# nRF24L01_RFX2401_SMD_0603.net
KiCad netlist of a schematic drawn in EAGLE
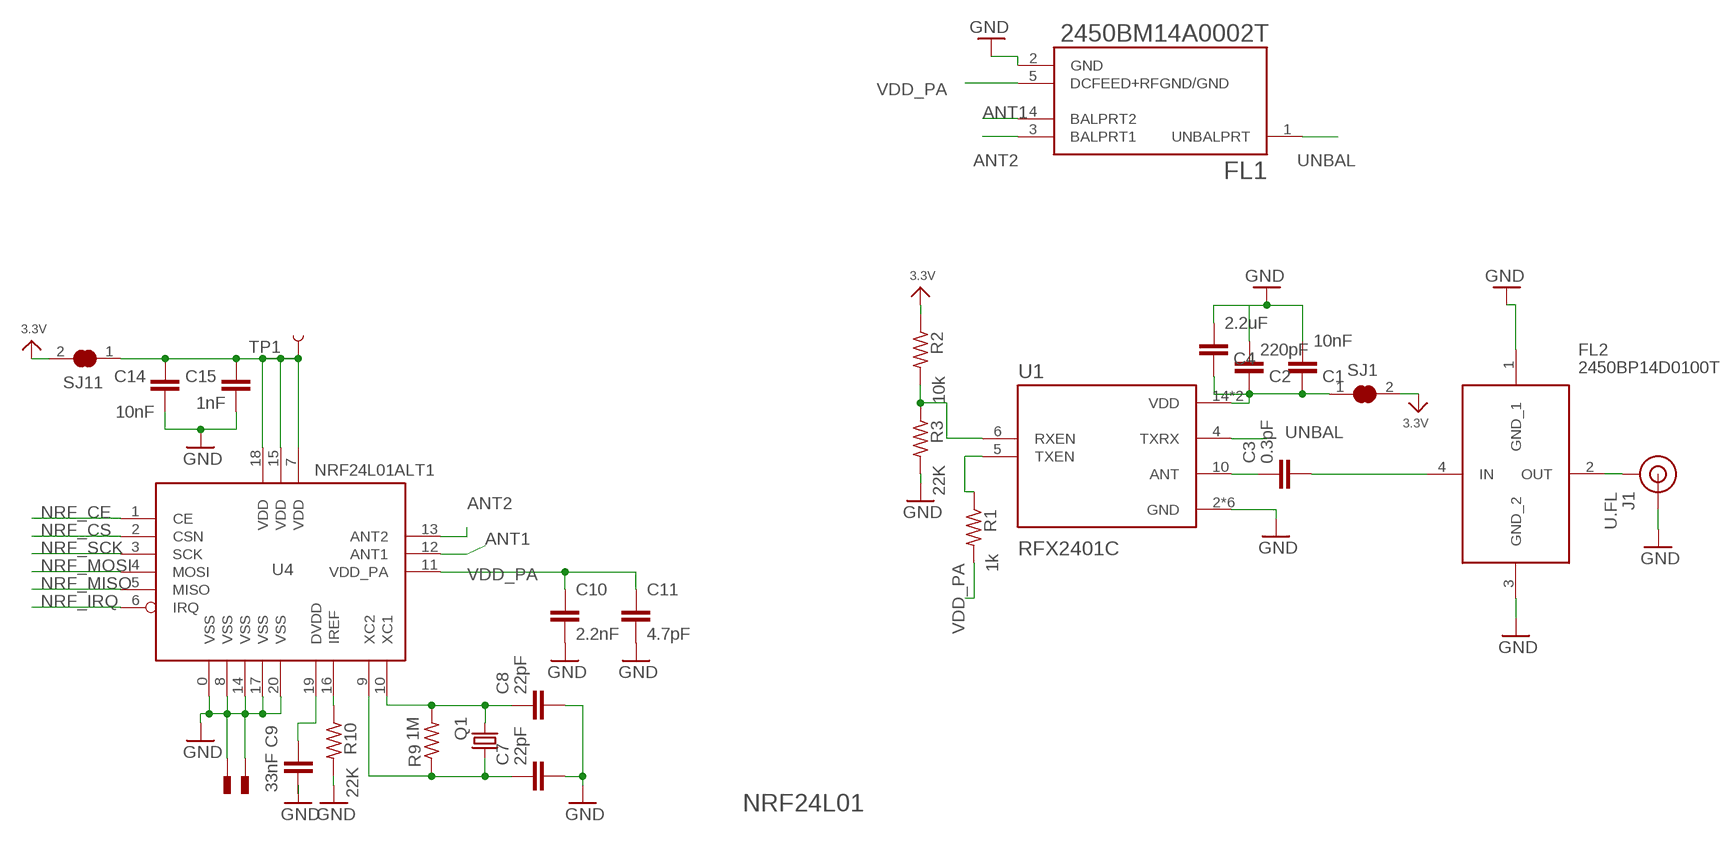
[diagram p0: schematic, sheet 1]

(export (version "E")
  (design (tool "Eeschema 10.0.6"))
  (components
    (comp (ref "C1")
      (value "10nF")
      (footprint "eagle-import:C0603")
      (libsource (lib "eagle-import") (part "C-EUC0603"))
    )
    (comp (ref "C2")
      (value "220pF")
      (footprint "eagle-import:C0603")
      (libsource (lib "eagle-import") (part "C-EUC0603"))
    )
    (comp (ref "C3")
      (value "0.3pF")
      (footprint "eagle-import:C0603")
      (libsource (lib "eagle-import") (part "C-EUC0603"))
    )
    (comp (ref "C4")
      (value "2.2uF")
      (footprint "eagle-import:C0603")
      (libsource (lib "eagle-import") (part "C-EUC0603"))
    )
    (comp (ref "C7")
      (value "22pF")
      (footprint "eagle-import:C0603")
      (libsource (lib "eagle-import") (part "C-EUC0603"))
    )
    (comp (ref "C8")
      (value "22pF")
      (footprint "eagle-import:C0603")
      (libsource (lib "eagle-import") (part "C-EUC0603"))
    )
    (comp (ref "C9")
      (value "33nF")
      (footprint "eagle-import:C0603")
      (libsource (lib "eagle-import") (part "C-EUC0603"))
    )
    (comp (ref "C10")
      (value "2.2nF")
      (footprint "eagle-import:C0603")
      (libsource (lib "eagle-import") (part "C-EUC0603"))
    )
    (comp (ref "C11")
      (value "4.7pF")
      (footprint "eagle-import:C0603")
      (libsource (lib "eagle-import") (part "C-EUC0603"))
    )
    (comp (ref "C14")
      (value "10nF")
      (footprint "eagle-import:C0603")
      (libsource (lib "eagle-import") (part "C-EUC0603"))
    )
    (comp (ref "C15")
      (value "1nF")
      (footprint "eagle-import:C0603")
      (libsource (lib "eagle-import") (part "C-EUC0603"))
    )
    (comp (ref "FL1")
      (value "2450BM14A0002T")
      (footprint "eagle-import:FIL_2450BM14A0002T")
      (fields (field (name "MF") "Johanson Technology"))
      (libsource (lib "eagle-import") (part "2450BM14A0002T"))
    )
    (comp (ref "FL2")
      (value "2450BP14D0100T")
      (footprint "eagle-import:2450BP14D0100T")
      (fields (field (name "MOUSER_PART_NUMBER") "609-2450BP14D0100T"))
      (libsource (lib "eagle-import") (part "2450BP14D0100T"))
    )
    (comp (ref "J1")
      (value "U.FL")
      (footprint "eagle-import:U.FL")
      (libsource (lib "eagle-import") (part "U.FL2PIN"))
    )
    (comp (ref "Q1")
      (value "KX-7")
      (footprint "eagle-import:3.2X2.5_KX-7")
      (libsource (lib "eagle-import") (part "KX-7"))
    )
    (comp (ref "R1")
      (value "1k")
      (footprint "eagle-import:R0603")
      (libsource (lib "eagle-import") (part "R-US_R0603"))
    )
    (comp (ref "R2")
      (value "10k")
      (footprint "eagle-import:R0603")
      (libsource (lib "eagle-import") (part "R-US_R0603"))
    )
    (comp (ref "R3")
      (value "22K")
      (footprint "eagle-import:R0603")
      (libsource (lib "eagle-import") (part "R-US_R0603"))
    )
    (comp (ref "R9")
      (value "1M")
      (footprint "eagle-import:R0603")
      (libsource (lib "eagle-import") (part "R-US_R0603"))
    )
    (comp (ref "R10")
      (value "22K")
      (footprint "eagle-import:R0603")
      (libsource (lib "eagle-import") (part "R-US_R0603"))
    )
    (comp (ref "SJ1")
      (value "SOLDERJUMPER_CLOSED")
      (footprint "eagle-import:SOLDERJUMPER_CLOSEDWIRE")
      (libsource (lib "eagle-import") (part "SOLDERJUMPER_CLOSED"))
    )
    (comp (ref "SJ11")
      (value "SOLDERJUMPER_CLOSED")
      (footprint "eagle-import:SOLDERJUMPER_CLOSEDWIRE")
      (libsource (lib "eagle-import") (part "SOLDERJUMPER_CLOSED"))
    )
    (comp (ref "TP1")
      (value "TEST-POINT3X5")
      (footprint "eagle-import:PAD.03X.05")
      (libsource (lib "eagle-import") (part "TEST-POINT3X5"))
    )
    (comp (ref "U$27")
      (value "PAD")
      (footprint "eagle-import:PAD-0.008")
      (libsource (lib "eagle-import") (part "PAD"))
    )
    (comp (ref "U$28")
      (value "PAD")
      (footprint "eagle-import:PAD-0.008")
      (libsource (lib "eagle-import") (part "PAD"))
    )
    (comp (ref "U1")
      (value "RFX2401C")
      (footprint "eagle-import:QFN50P300X300X60-17N")
      (fields (field (name "MF") "Skyworks Solutions"))
      (libsource (lib "eagle-import") (part "RFX2401C"))
    )
    (comp (ref "U4")
      (value "NRF24L01ALT1")
      (footprint "eagle-import:QFN20_ALT1")
      (libsource (lib "eagle-import") (part "NRF24L01ALT1"))
    )
  )
  (nets
    (net (code "1") (name "/ANT1") (class "Default")
      (node (ref "FL1") (pin "4") (pinfunction "BALPRT2_4") (pintype "passive"))
      (node (ref "U4") (pin "12") (pinfunction "ANT1_12") (pintype "output"))
    )
    (net (code "2") (name "/ANT2") (class "Default")
      (node (ref "FL1") (pin "3") (pinfunction "BALPRT1_3") (pintype "passive"))
      (node (ref "U4") (pin "13") (pinfunction "ANT2_13") (pintype "output"))
    )
    (net (code "3") (name "/NRF_CE") (class "Default")
      (node (ref "U4") (pin "1") (pinfunction "CE_1") (pintype "input"))
    )
    (net (code "4") (name "/NRF_CS") (class "Default")
      (node (ref "U4") (pin "2") (pinfunction "CSN_2") (pintype "input"))
    )
    (net (code "5") (name "/NRF_IRQ") (class "Default")
      (node (ref "U4") (pin "6") (pinfunction "IRQ_6") (pintype "output"))
    )
    (net (code "6") (name "/NRF_MISO") (class "Default")
      (node (ref "U4") (pin "5") (pinfunction "MISO_5") (pintype "output"))
    )
    (net (code "7") (name "/NRF_MOSI") (class "Default")
      (node (ref "U4") (pin "4") (pinfunction "MOSI_4") (pintype "input"))
    )
    (net (code "8") (name "/NRF_SCK") (class "Default")
      (node (ref "U4") (pin "3") (pinfunction "SCK_3") (pintype "input"))
    )
    (net (code "9") (name "/UNBAL") (class "Default")
      (node (ref "FL1") (pin "1") (pinfunction "UNBALPRT_1") (pintype "passive"))
      (node (ref "U1") (pin "4") (pinfunction "TXRX_4") (pintype "bidirectional"))
    )
    (net (code "10") (name "/VDD_PA") (class "Default")
      (node (ref "C10") (pin "1") (pinfunction "1_1") (pintype "passive"))
      (node (ref "C11") (pin "1") (pinfunction "1_1") (pintype "passive"))
      (node (ref "FL1") (pin "5") (pinfunction "DCFEED+RFGND/GND_5") (pintype "power_in"))
      (node (ref "R1") (pin "2") (pinfunction "2_2") (pintype "passive"))
      (node (ref "U4") (pin "11") (pinfunction "VDD_PA_11") (pintype "power_in"))
    )
    (net (code "11") (name "3.3V") (class "Default")
      (node (ref "R2") (pin "1") (pinfunction "1_1") (pintype "passive"))
      (node (ref "SJ1") (pin "2") (pinfunction "2_2") (pintype "passive"))
      (node (ref "SJ11") (pin "2") (pinfunction "2_2") (pintype "passive"))
    )
    (net (code "12") (name "GND") (class "Default")
      (node (ref "C1") (pin "1") (pinfunction "1_1") (pintype "passive"))
      (node (ref "C10") (pin "2") (pinfunction "2_2") (pintype "passive"))
      (node (ref "C11") (pin "2") (pinfunction "2_2") (pintype "passive"))
      (node (ref "C14") (pin "1") (pinfunction "1_1") (pintype "passive"))
      (node (ref "C15") (pin "1") (pinfunction "1_1") (pintype "passive"))
      (node (ref "C2") (pin "1") (pinfunction "1_1") (pintype "passive"))
      (node (ref "C4") (pin "1") (pinfunction "1_1") (pintype "passive"))
      (node (ref "C7") (pin "2") (pinfunction "2_2") (pintype "passive"))
      (node (ref "C8") (pin "2") (pinfunction "2_2") (pintype "passive"))
      (node (ref "C9") (pin "2") (pinfunction "2_2") (pintype "passive"))
      (node (ref "FL1") (pin "2") (pinfunction "GND_2") (pintype "power_in"))
      (node (ref "FL2") (pin "1") (pinfunction "GND_1_1") (pintype "bidirectional"))
      (node (ref "FL2") (pin "3") (pinfunction "GND_2_3") (pintype "bidirectional"))
      (node (ref "J1") (pin "FEED") (pinfunction "SIGNAL_FEED") (pintype "bidirectional"))
      (node (ref "R10") (pin "2") (pinfunction "2_2") (pintype "passive"))
      (node (ref "R3") (pin "2") (pinfunction "2_2") (pintype "passive"))
      (node (ref "U$27") (pin "P$1") (pinfunction "P$1_P$1") (pintype "bidirectional"))
      (node (ref "U$28") (pin "P$1") (pinfunction "P$1_P$1") (pintype "bidirectional"))
      (node (ref "U1") (pin "11") (pinfunction "GND_11") (pintype "power_in"))
      (node (ref "U1") (pin "17") (pinfunction "GND_17") (pintype "power_in"))
      (node (ref "U1") (pin "2") (pinfunction "GND_2") (pintype "power_in"))
      (node (ref "U1") (pin "3") (pinfunction "GND_3") (pintype "power_in"))
      (node (ref "U1") (pin "8") (pinfunction "GND_8") (pintype "power_in"))
      (node (ref "U1") (pin "9") (pinfunction "GND_9") (pintype "power_in"))
      (node (ref "U4") (pin "0") (pinfunction "VSS_0") (pintype "power_in"))
      (node (ref "U4") (pin "14") (pinfunction "VSS_14") (pintype "power_in"))
      (node (ref "U4") (pin "17") (pinfunction "VSS_17") (pintype "power_in"))
      (node (ref "U4") (pin "20") (pinfunction "VSS_20") (pintype "power_in"))
      (node (ref "U4") (pin "8") (pinfunction "VSS_8") (pintype "power_in"))
    )
    (net (code "13") (name "Net-(C1-Pad2)") (class "Default")
      (node (ref "C1") (pin "2") (pinfunction "2_2") (pintype "passive"))
      (node (ref "C2") (pin "2") (pinfunction "2_2") (pintype "passive"))
      (node (ref "C4") (pin "2") (pinfunction "2_2") (pintype "passive"))
      (node (ref "SJ1") (pin "1") (pinfunction "1_1") (pintype "passive"))
      (node (ref "U1") (pin "14") (pinfunction "VDD_14") (pintype "power_in"))
      (node (ref "U1") (pin "16") (pinfunction "VDD_16") (pintype "power_in"))
    )
    (net (code "14") (name "Net-(FL2-IN)") (class "Default")
      (node (ref "C3") (pin "2") (pinfunction "2_2") (pintype "passive"))
      (node (ref "FL2") (pin "4") (pinfunction "IN_4") (pintype "bidirectional"))
    )
    (net (code "15") (name "Net-(FL2-OUT)") (class "Default")
      (node (ref "FL2") (pin "2") (pinfunction "OUT_2") (pintype "bidirectional"))
      (node (ref "J1") (pin "1") (pinfunction "GND_1") (pintype "bidirectional"))
      (node (ref "J1") (pin "2") (pinfunction "GND_2") (pintype "bidirectional"))
    )
    (net (code "16") (name "Net-(Q1-2)") (class "Default")
      (node (ref "C8") (pin "1") (pinfunction "1_1") (pintype "passive"))
      (node (ref "Q1") (pin "3") (pinfunction "2_3") (pintype "passive"))
      (node (ref "R9") (pin "2") (pinfunction "2_2") (pintype "passive"))
      (node (ref "U4") (pin "10") (pinfunction "XC1_10") (pintype "input"))
    )
    (net (code "17") (name "Net-(TP1-1)") (class "Default")
      (node (ref "C14") (pin "2") (pinfunction "2_2") (pintype "passive"))
      (node (ref "C15") (pin "2") (pinfunction "2_2") (pintype "passive"))
      (node (ref "SJ11") (pin "1") (pinfunction "1_1") (pintype "passive"))
      (node (ref "TP1") (pin "P$1") (pinfunction "1_P$1") (pintype "bidirectional"))
      (node (ref "U4") (pin "15") (pinfunction "VDD_15") (pintype "power_in"))
      (node (ref "U4") (pin "18") (pinfunction "VDD_18") (pintype "power_in"))
      (node (ref "U4") (pin "7") (pinfunction "VDD_7") (pintype "power_in"))
    )
    (net (code "18") (name "Net-(U1-ANT)") (class "Default")
      (node (ref "C3") (pin "1") (pinfunction "1_1") (pintype "passive"))
      (node (ref "U1") (pin "10") (pinfunction "ANT_10") (pintype "passive"))
    )
    (net (code "19") (name "Net-(U1-RXEN)") (class "Default")
      (node (ref "R2") (pin "2") (pinfunction "2_2") (pintype "passive"))
      (node (ref "R3") (pin "1") (pinfunction "1_1") (pintype "passive"))
      (node (ref "U1") (pin "6") (pinfunction "RXEN_6") (pintype "input"))
    )
    (net (code "20") (name "Net-(U1-TXEN)") (class "Default")
      (node (ref "R1") (pin "1") (pinfunction "1_1") (pintype "passive"))
      (node (ref "U1") (pin "5") (pinfunction "TXEN_5") (pintype "input"))
    )
    (net (code "21") (name "Net-(U4-DVDD)") (class "Default")
      (node (ref "C9") (pin "1") (pinfunction "1_1") (pintype "passive"))
      (node (ref "U4") (pin "19") (pinfunction "DVDD_19") (pintype "power_in"))
    )
    (net (code "22") (name "Net-(U4-IREF)") (class "Default")
      (node (ref "R10") (pin "1") (pinfunction "1_1") (pintype "passive"))
      (node (ref "U4") (pin "16") (pinfunction "IREF_16") (pintype "input"))
    )
    (net (code "23") (name "Net-(U4-XC2)") (class "Default")
      (node (ref "C7") (pin "1") (pinfunction "1_1") (pintype "passive"))
      (node (ref "Q1") (pin "1") (pinfunction "1_1") (pintype "passive"))
      (node (ref "R9") (pin "1") (pinfunction "1_1") (pintype "passive"))
      (node (ref "U4") (pin "9") (pinfunction "XC2_9") (pintype "input"))
    )
  )
)
